# SCH_New_Project_2022-06-30.net
KiCad netlist of a schematic drawn in EasyEDA
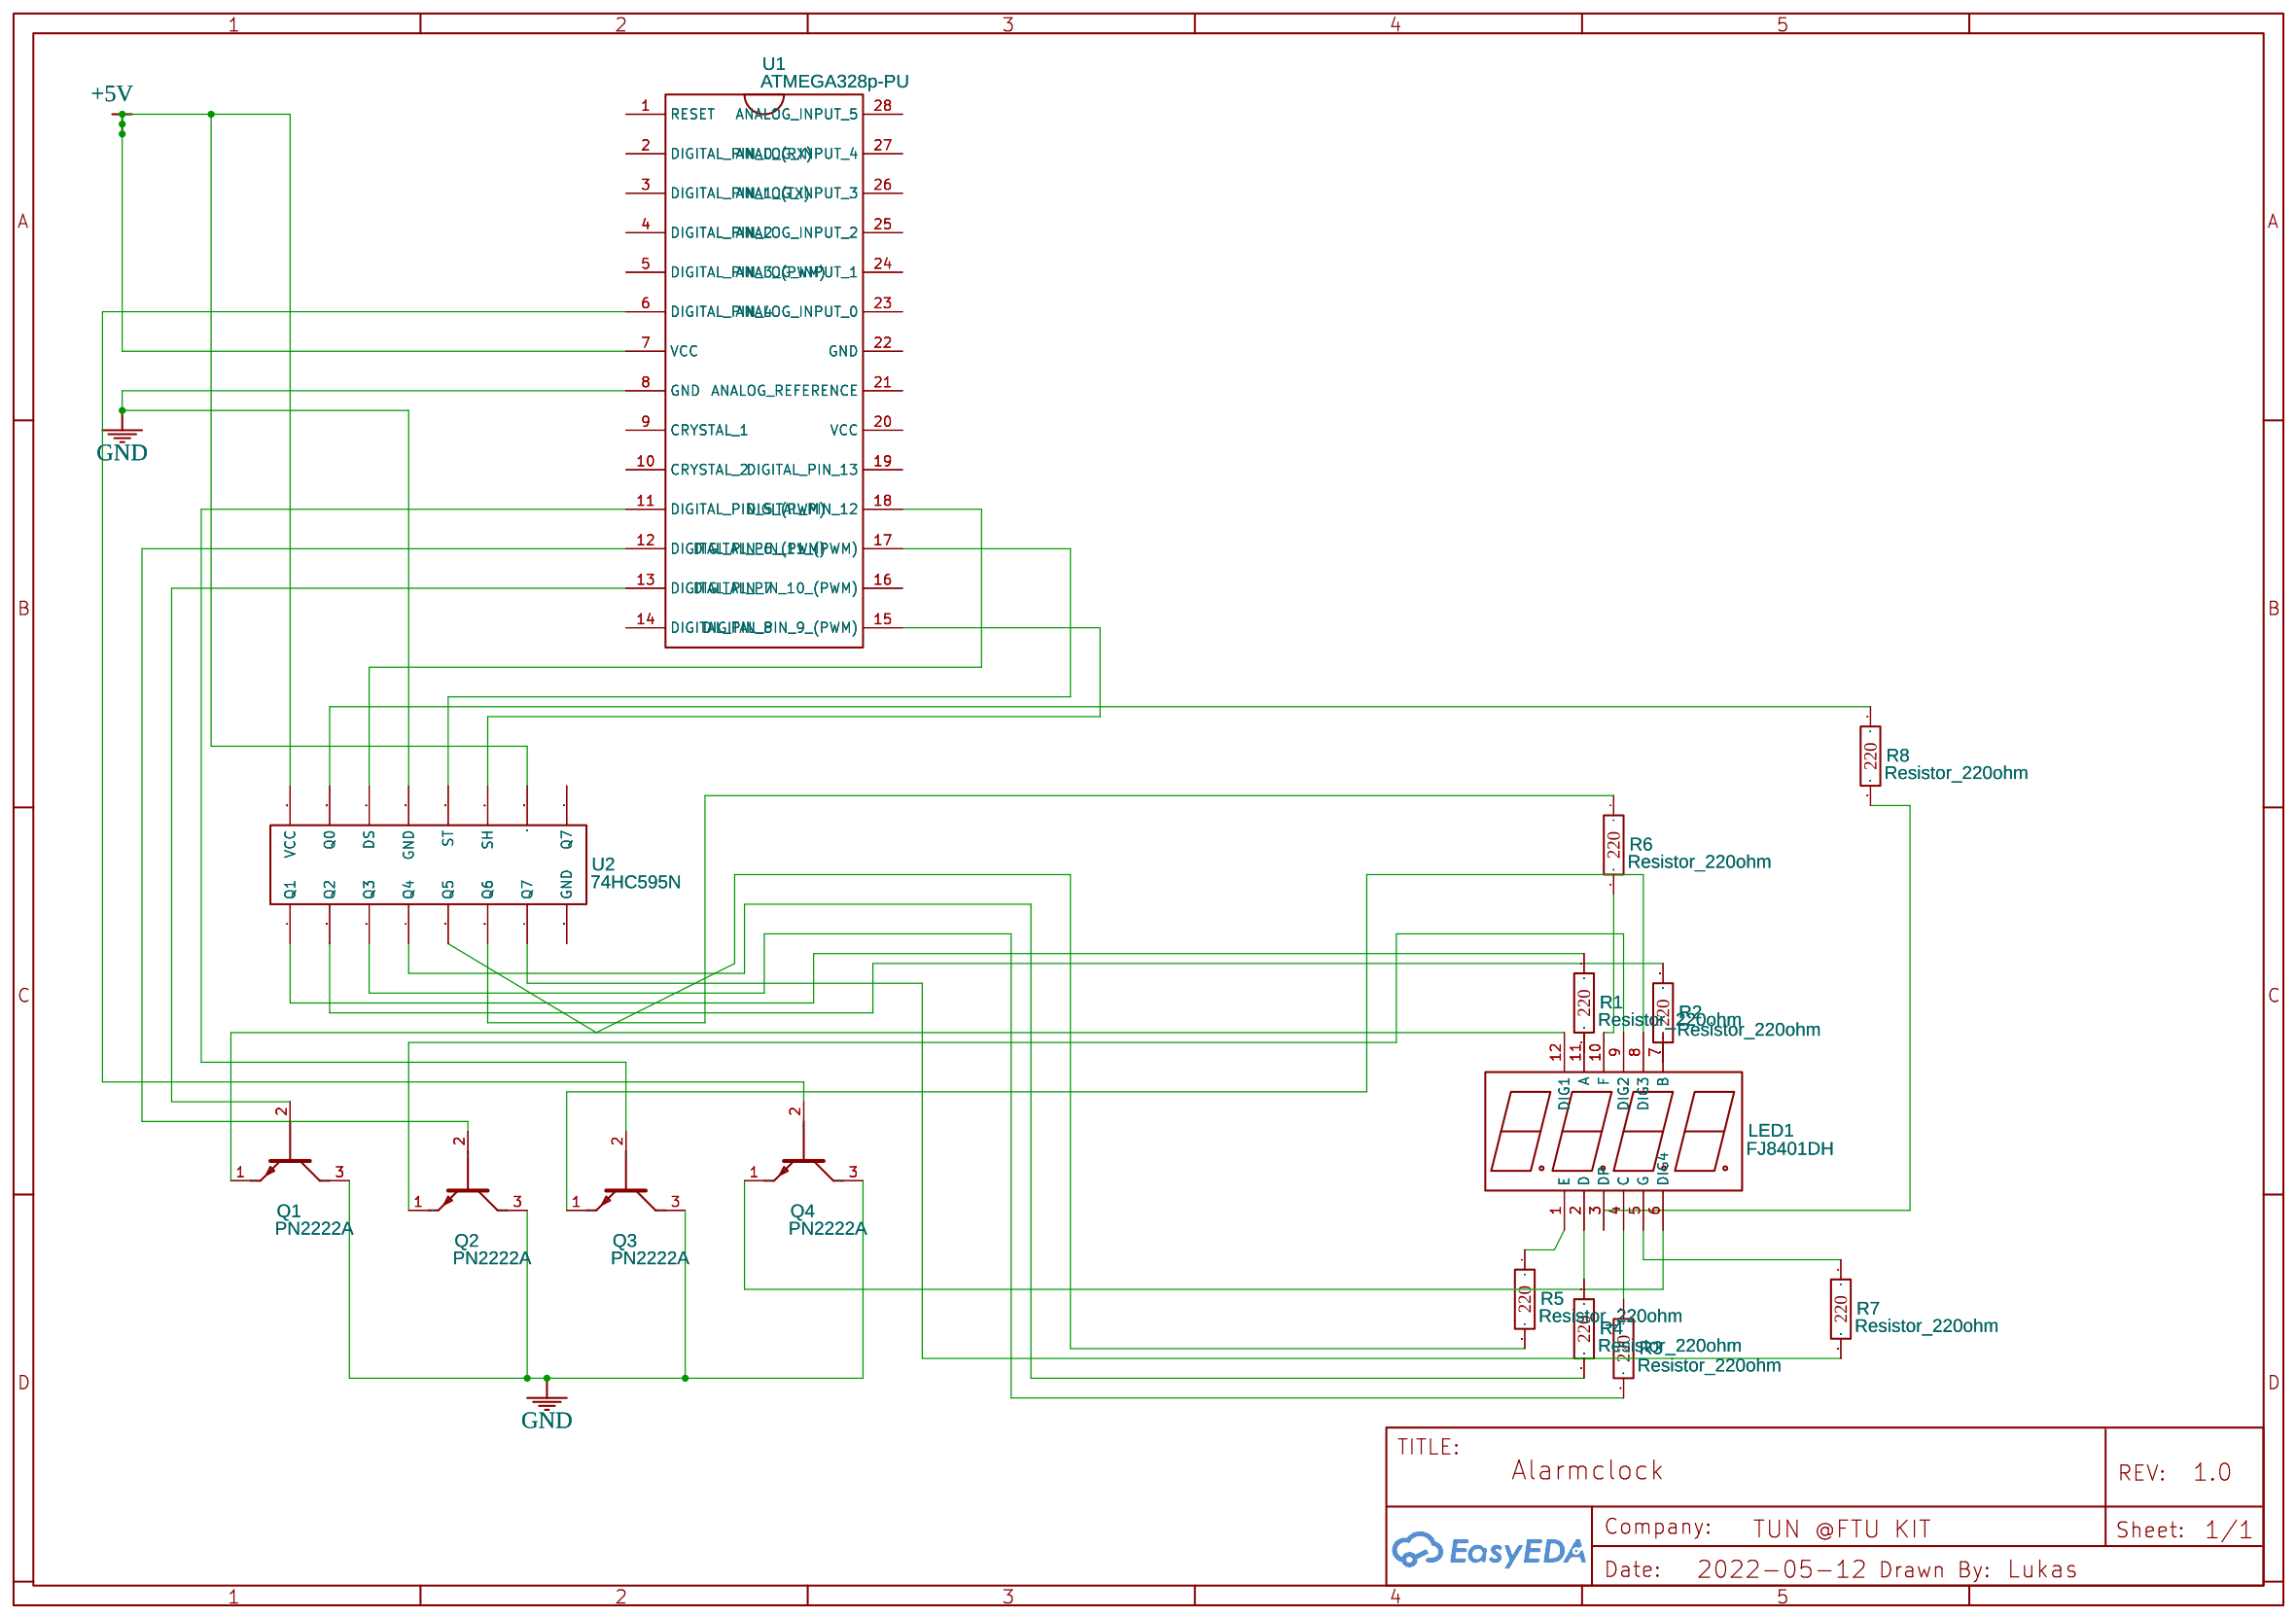
[diagram p0: schematic sheet]

(export (version "E")
  (design (tool "Eeschema 10.0.6"))
  (components
    (comp (ref "LED1")
      (value "FJ8401DH")
      (fields (field (name "BOM_Supplier Part") "C70368"))
      (libsource (lib "") (part "FJ8401DH"))
    )
    (comp (ref "Q1") (value "PN2222A") (libsource (lib "") (part "PN2222A")))
    (comp (ref "Q2") (value "PN2222A") (libsource (lib "") (part "PN2222A")))
    (comp (ref "Q3") (value "PN2222A") (libsource (lib "") (part "PN2222A")))
    (comp (ref "Q4") (value "PN2222A") (libsource (lib "") (part "PN2222A")))
    (comp (ref "R1") (value "Resistor_220ohm") (libsource (lib "") (part "Resistor_220ohm")))
    (comp (ref "R2") (value "Resistor_220ohm") (libsource (lib "") (part "Resistor_220ohm")))
    (comp (ref "R3") (value "Resistor_220ohm") (libsource (lib "") (part "Resistor_220ohm")))
    (comp (ref "R4") (value "Resistor_220ohm") (libsource (lib "") (part "Resistor_220ohm")))
    (comp (ref "R5") (value "Resistor_220ohm") (libsource (lib "") (part "Resistor_220ohm")))
    (comp (ref "R6") (value "Resistor_220ohm") (libsource (lib "") (part "Resistor_220ohm")))
    (comp (ref "R7") (value "Resistor_220ohm") (libsource (lib "") (part "Resistor_220ohm")))
    (comp (ref "R8") (value "Resistor_220ohm") (libsource (lib "") (part "Resistor_220ohm")))
    (comp (ref "U1") (value "ATMEGA328p-PU") (libsource (lib "") (part "ATMEGA328p-PU")))
    (comp (ref "U2") (value "74HC595N") (libsource (lib "") (part "74HC595N")))
  )
  (nets
    (net (code "1") (name "+5V") (class "Default")
      (node (ref "U1") (pin "7") (pinfunction "VCC_7") (pintype "unspecified"))
      (node (ref "U2") (pin "10") (pinfunction "10_10") (pintype "unspecified"))
      (node (ref "U2") (pin "16") (pinfunction "VCC_16") (pintype "unspecified"))
    )
    (net (code "2") (name "GND") (class "Default")
      (node (ref "Q1") (pin "3") (pinfunction "C_3") (pintype "bidirectional"))
      (node (ref "Q2") (pin "3") (pinfunction "C_3") (pintype "bidirectional"))
      (node (ref "Q3") (pin "3") (pinfunction "C_3") (pintype "bidirectional"))
      (node (ref "Q4") (pin "3") (pinfunction "C_3") (pintype "bidirectional"))
      (node (ref "U1") (pin "8") (pinfunction "GND_8") (pintype "unspecified"))
      (node (ref "U2") (pin "13") (pinfunction "GND_13") (pintype "unspecified"))
    )
    (net (code "3") (name "Net-(LED1-A)") (class "Default")
      (node (ref "LED1") (pin "11") (pinfunction "A_11") (pintype "unspecified"))
      (node (ref "R1") (pin "2") (pinfunction "2_2") (pintype "unspecified"))
    )
    (net (code "4") (name "Net-(LED1-B)") (class "Default")
      (node (ref "LED1") (pin "7") (pinfunction "B_7") (pintype "unspecified"))
      (node (ref "R2") (pin "2") (pinfunction "2_2") (pintype "unspecified"))
    )
    (net (code "5") (name "Net-(LED1-C)") (class "Default")
      (node (ref "LED1") (pin "4") (pinfunction "C_4") (pintype "unspecified"))
      (node (ref "R3") (pin "1") (pinfunction "1_1") (pintype "unspecified"))
    )
    (net (code "6") (name "Net-(LED1-D)") (class "Default")
      (node (ref "LED1") (pin "2") (pinfunction "D_2") (pintype "unspecified"))
      (node (ref "R4") (pin "1") (pinfunction "1_1") (pintype "unspecified"))
    )
    (net (code "7") (name "Net-(LED1-DIG1)") (class "Default")
      (node (ref "LED1") (pin "12") (pinfunction "DIG1_12") (pintype "unspecified"))
      (node (ref "Q1") (pin "1") (pinfunction "E_1") (pintype "bidirectional"))
    )
    (net (code "8") (name "Net-(LED1-DIG2)") (class "Default")
      (node (ref "LED1") (pin "9") (pinfunction "DIG2_9") (pintype "unspecified"))
      (node (ref "Q2") (pin "1") (pinfunction "E_1") (pintype "bidirectional"))
    )
    (net (code "9") (name "Net-(LED1-DIG3)") (class "Default")
      (node (ref "LED1") (pin "8") (pinfunction "DIG3_8") (pintype "unspecified"))
      (node (ref "Q3") (pin "1") (pinfunction "E_1") (pintype "bidirectional"))
    )
    (net (code "10") (name "Net-(LED1-DIG4)") (class "Default")
      (node (ref "LED1") (pin "6") (pinfunction "DIG4_6") (pintype "unspecified"))
      (node (ref "Q4") (pin "1") (pinfunction "E_1") (pintype "bidirectional"))
    )
    (net (code "11") (name "Net-(LED1-DP)") (class "Default")
      (node (ref "LED1") (pin "3") (pinfunction "DP_3") (pintype "unspecified"))
      (node (ref "R8") (pin "2") (pinfunction "2_2") (pintype "unspecified"))
    )
    (net (code "12") (name "Net-(LED1-E)") (class "Default")
      (node (ref "LED1") (pin "1") (pinfunction "E_1") (pintype "unspecified"))
      (node (ref "R5") (pin "1") (pinfunction "1_1") (pintype "unspecified"))
    )
    (net (code "13") (name "Net-(LED1-F)") (class "Default")
      (node (ref "LED1") (pin "10") (pinfunction "F_10") (pintype "unspecified"))
      (node (ref "R6") (pin "2") (pinfunction "2_2") (pintype "unspecified"))
    )
    (net (code "14") (name "Net-(LED1-G)") (class "Default")
      (node (ref "LED1") (pin "5") (pinfunction "G_5") (pintype "unspecified"))
      (node (ref "R7") (pin "1") (pinfunction "1_1") (pintype "unspecified"))
    )
    (net (code "15") (name "Net-(Q1-B)") (class "Default")
      (node (ref "Q1") (pin "2") (pinfunction "B_2") (pintype "bidirectional"))
      (node (ref "U1") (pin "13") (pinfunction "DIGITAL_PIN_7_13") (pintype "unspecified"))
    )
    (net (code "16") (name "Net-(Q2-B)") (class "Default")
      (node (ref "Q2") (pin "2") (pinfunction "B_2") (pintype "bidirectional"))
      (node (ref "U1") (pin "12") (pinfunction "DIGITAL_PIN_6_(PWM)_12") (pintype "unspecified"))
    )
    (net (code "17") (name "Net-(Q3-B)") (class "Default")
      (node (ref "Q3") (pin "2") (pinfunction "B_2") (pintype "bidirectional"))
      (node (ref "U1") (pin "11") (pinfunction "DIGITAL_PIN_5_(PWM)_11") (pintype "unspecified"))
    )
    (net (code "18") (name "Net-(Q4-B)") (class "Default")
      (node (ref "Q4") (pin "2") (pinfunction "B_2") (pintype "bidirectional"))
      (node (ref "U1") (pin "6") (pinfunction "DIGITAL_PIN_4_6") (pintype "unspecified"))
    )
    (net (code "19") (name "Net-(R7-Pad2)") (class "Default")
      (node (ref "R7") (pin "2") (pinfunction "2_2") (pintype "unspecified"))
      (node (ref "U2") (pin "7") (pinfunction "Q7_7") (pintype "unspecified"))
    )
    (net (code "20") (name "Net-(U1-DIGITAL_PIN_9_(PWM))") (class "Default")
      (node (ref "U1") (pin "15") (pinfunction "DIGITAL_PIN_9_(PWM)_15") (pintype "unspecified"))
      (node (ref "U2") (pin "11") (pinfunction "SH_11") (pintype "unspecified"))
    )
    (net (code "21") (name "Net-(U1-DIGITAL_PIN_11_(PWM))") (class "Default")
      (node (ref "U1") (pin "17") (pinfunction "DIGITAL_PIN_11_(PWM)_17") (pintype "unspecified"))
      (node (ref "U2") (pin "12") (pinfunction "ST_12") (pintype "unspecified"))
    )
    (net (code "22") (name "Net-(U1-DIGITAL_PIN_12)") (class "Default")
      (node (ref "U1") (pin "18") (pinfunction "DIGITAL_PIN_12_18") (pintype "unspecified"))
      (node (ref "U2") (pin "14") (pinfunction "DS_14") (pintype "unspecified"))
    )
    (net (code "23") (name "Net-(U2-Q0)") (class "Default")
      (node (ref "R8") (pin "1") (pinfunction "1_1") (pintype "unspecified"))
      (node (ref "U2") (pin "15") (pinfunction "Q0_15") (pintype "unspecified"))
    )
    (net (code "24") (name "Net-(U2-Q1)") (class "Default")
      (node (ref "R1") (pin "1") (pinfunction "1_1") (pintype "unspecified"))
      (node (ref "U2") (pin "1") (pinfunction "Q1_1") (pintype "unspecified"))
    )
    (net (code "25") (name "Net-(U2-Q2)") (class "Default")
      (node (ref "R2") (pin "1") (pinfunction "1_1") (pintype "unspecified"))
      (node (ref "U2") (pin "2") (pinfunction "Q2_2") (pintype "unspecified"))
    )
    (net (code "26") (name "Net-(U2-Q3)") (class "Default")
      (node (ref "R3") (pin "2") (pinfunction "2_2") (pintype "unspecified"))
      (node (ref "U2") (pin "3") (pinfunction "Q3_3") (pintype "unspecified"))
    )
    (net (code "27") (name "Net-(U2-Q4)") (class "Default")
      (node (ref "R4") (pin "2") (pinfunction "2_2") (pintype "unspecified"))
      (node (ref "U2") (pin "4") (pinfunction "Q4_4") (pintype "unspecified"))
    )
    (net (code "28") (name "Net-(U2-Q5)") (class "Default")
      (node (ref "R5") (pin "2") (pinfunction "2_2") (pintype "unspecified"))
      (node (ref "U2") (pin "5") (pinfunction "Q5_5") (pintype "unspecified"))
    )
    (net (code "29") (name "Net-(U2-Q6)") (class "Default")
      (node (ref "R6") (pin "1") (pinfunction "1_1") (pintype "unspecified"))
      (node (ref "U2") (pin "6") (pinfunction "Q6_6") (pintype "unspecified"))
    )
    (net (code "30") (name "unconnected-(U1-ANALOG_INPUT_0-Pad23)") (class "Default")
      (node (ref "U1") (pin "23") (pinfunction "ANALOG_INPUT_0_23") (pintype "unspecified"))
    )
    (net (code "31") (name "unconnected-(U1-ANALOG_INPUT_1-Pad24)") (class "Default")
      (node (ref "U1") (pin "24") (pinfunction "ANALOG_INPUT_1_24") (pintype "unspecified"))
    )
    (net (code "32") (name "unconnected-(U1-ANALOG_INPUT_2-Pad25)") (class "Default")
      (node (ref "U1") (pin "25") (pinfunction "ANALOG_INPUT_2_25") (pintype "unspecified"))
    )
    (net (code "33") (name "unconnected-(U1-ANALOG_INPUT_3-Pad26)") (class "Default")
      (node (ref "U1") (pin "26") (pinfunction "ANALOG_INPUT_3_26") (pintype "unspecified"))
    )
    (net (code "34") (name "unconnected-(U1-ANALOG_INPUT_4-Pad27)") (class "Default")
      (node (ref "U1") (pin "27") (pinfunction "ANALOG_INPUT_4_27") (pintype "unspecified"))
    )
    (net (code "35") (name "unconnected-(U1-ANALOG_INPUT_5-Pad28)") (class "Default")
      (node (ref "U1") (pin "28") (pinfunction "ANALOG_INPUT_5_28") (pintype "unspecified"))
    )
    (net (code "36") (name "unconnected-(U1-ANALOG_REFERENCE-Pad21)") (class "Default")
      (node (ref "U1") (pin "21") (pinfunction "ANALOG_REFERENCE_21") (pintype "unspecified"))
    )
    (net (code "37") (name "unconnected-(U1-CRYSTAL_1-Pad9)") (class "Default")
      (node (ref "U1") (pin "9") (pinfunction "CRYSTAL_1_9") (pintype "unspecified"))
    )
    (net (code "38") (name "unconnected-(U1-CRYSTAL_2-Pad10)") (class "Default")
      (node (ref "U1") (pin "10") (pinfunction "CRYSTAL_2_10") (pintype "unspecified"))
    )
    (net (code "39") (name "unconnected-(U1-DIGITAL_PIN_0_(RX)-Pad2)") (class "Default")
      (node (ref "U1") (pin "2") (pinfunction "DIGITAL_PIN_0_(RX)_2") (pintype "unspecified"))
    )
    (net (code "40") (name "unconnected-(U1-DIGITAL_PIN_1_(TX)-Pad3)") (class "Default")
      (node (ref "U1") (pin "3") (pinfunction "DIGITAL_PIN_1_(TX)_3") (pintype "unspecified"))
    )
    (net (code "41") (name "unconnected-(U1-DIGITAL_PIN_2-Pad4)") (class "Default")
      (node (ref "U1") (pin "4") (pinfunction "DIGITAL_PIN_2_4") (pintype "unspecified"))
    )
    (net (code "42") (name "unconnected-(U1-DIGITAL_PIN_3_(PWM)-Pad5)") (class "Default")
      (node (ref "U1") (pin "5") (pinfunction "DIGITAL_PIN_3_(PWM)_5") (pintype "unspecified"))
    )
    (net (code "43") (name "unconnected-(U1-DIGITAL_PIN_8-Pad14)") (class "Default")
      (node (ref "U1") (pin "14") (pinfunction "DIGITAL_PIN_8_14") (pintype "unspecified"))
    )
    (net (code "44") (name "unconnected-(U1-DIGITAL_PIN_10_(PWM)-Pad16)") (class "Default")
      (node (ref "U1") (pin "16") (pinfunction "DIGITAL_PIN_10_(PWM)_16") (pintype "unspecified"))
    )
    (net (code "45") (name "unconnected-(U1-DIGITAL_PIN_13-Pad19)") (class "Default")
      (node (ref "U1") (pin "19") (pinfunction "DIGITAL_PIN_13_19") (pintype "unspecified"))
    )
    (net (code "46") (name "unconnected-(U1-GND-Pad22)") (class "Default")
      (node (ref "U1") (pin "22") (pinfunction "GND_22") (pintype "unspecified"))
    )
    (net (code "47") (name "unconnected-(U1-RESET-Pad1)") (class "Default")
      (node (ref "U1") (pin "1") (pinfunction "RESET_1") (pintype "unspecified"))
    )
    (net (code "48") (name "unconnected-(U1-VCC-Pad20)") (class "Default")
      (node (ref "U1") (pin "20") (pinfunction "VCC_20") (pintype "unspecified"))
    )
    (net (code "49") (name "unconnected-(U2-GND-Pad8)") (class "Default")
      (node (ref "U2") (pin "8") (pinfunction "GND_8") (pintype "unspecified"))
    )
    (net (code "50") (name "unconnected-(U2-Q7-Pad9)") (class "Default")
      (node (ref "U2") (pin "9") (pinfunction "Q7_9") (pintype "unspecified"))
    )
  )
)
